# STM32F103Core.net
KiCad netlist of a schematic drawn in Altium Designer
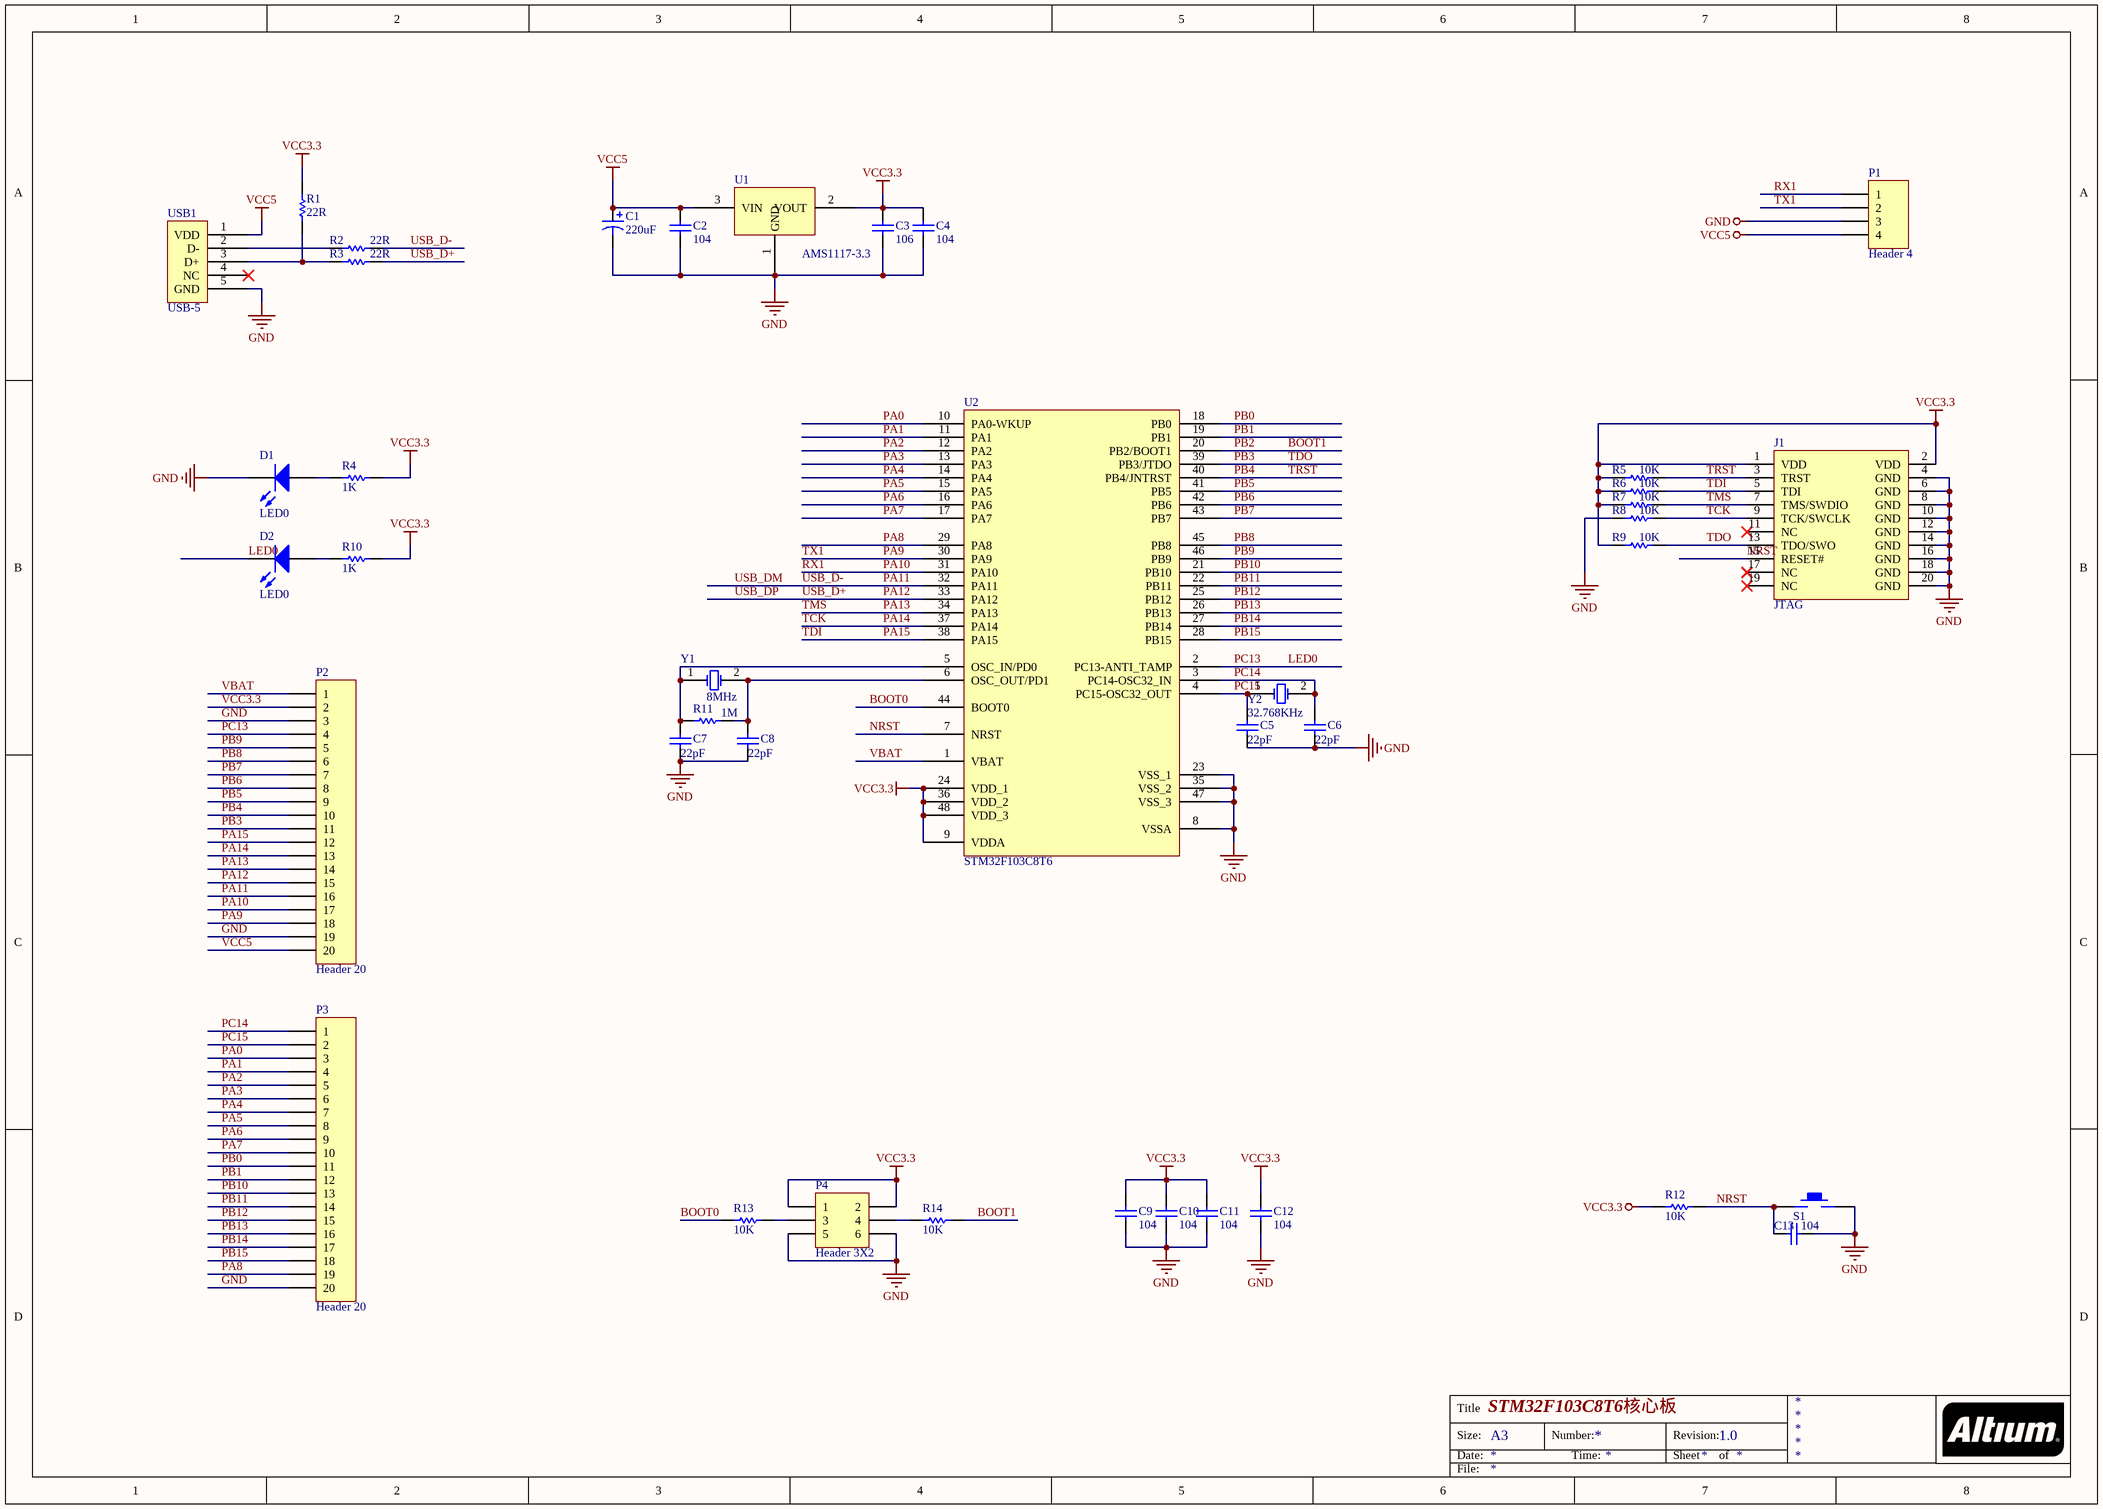
[diagram p0: STM32F103Core.SchDoc]

(export (version "E")
  (design (tool "Eeschema 10.0.6"))
  (components
    (comp (ref "C1")
      (value "220uF")
      (footprint "TAJ-B")
      (description "Cap Pol2")
      (fields (field (name "PUBLISHER") "Altium Limited"))
      (libsource (lib "STM32F103Core") (part "Cap Pol2"))
    )
    (comp (ref "C2")
      (value "104")
      (footprint "C0805")
      (description "Capacitor")
      (fields (field (name "PUBLISHER") "Altium Limited"))
      (libsource (lib "STM32F103Core") (part "C"))
    )
    (comp (ref "C3")
      (value "106")
      (footprint "C0805")
      (description "Capacitor")
      (fields (field (name "PUBLISHER") "Altium Limited"))
      (libsource (lib "STM32F103Core") (part "C"))
    )
    (comp (ref "C4")
      (value "104")
      (footprint "C0805")
      (description "Capacitor")
      (fields (field (name "PUBLISHER") "Altium Limited"))
      (libsource (lib "STM32F103Core") (part "C"))
    )
    (comp (ref "C5")
      (value "22pF")
      (footprint "C0805")
      (description "Capacitor")
      (fields (field (name "PUBLISHER") "Altium Limited"))
      (libsource (lib "STM32F103Core") (part "C"))
    )
    (comp (ref "C6")
      (value "22pF")
      (footprint "C0805")
      (description "Capacitor")
      (fields (field (name "PUBLISHER") "Altium Limited"))
      (libsource (lib "STM32F103Core") (part "C"))
    )
    (comp (ref "C7")
      (value "22pF")
      (footprint "C0805")
      (description "Capacitor")
      (fields (field (name "PUBLISHER") "Altium Limited"))
      (libsource (lib "STM32F103Core") (part "C"))
    )
    (comp (ref "C8")
      (value "22pF")
      (footprint "C0805")
      (description "Capacitor")
      (fields (field (name "PUBLISHER") "Altium Limited"))
      (libsource (lib "STM32F103Core") (part "C"))
    )
    (comp (ref "C9")
      (value "104")
      (footprint "C0805")
      (description "Capacitor")
      (fields (field (name "PUBLISHER") "Altium Limited"))
      (libsource (lib "STM32F103Core") (part "C"))
    )
    (comp (ref "C10")
      (value "104")
      (footprint "C0805")
      (description "Capacitor")
      (fields (field (name "PUBLISHER") "Altium Limited"))
      (libsource (lib "STM32F103Core") (part "C"))
    )
    (comp (ref "C11")
      (value "104")
      (footprint "C0805")
      (description "Capacitor")
      (fields (field (name "PUBLISHER") "Altium Limited"))
      (libsource (lib "STM32F103Core") (part "C"))
    )
    (comp (ref "C12")
      (value "104")
      (footprint "C0805")
      (description "Capacitor")
      (fields (field (name "PUBLISHER") "Altium Limited"))
      (libsource (lib "STM32F103Core") (part "C"))
    )
    (comp (ref "C13")
      (value "104")
      (footprint "C0805")
      (description "Capacitor")
      (fields (field (name "PUBLISHER") "Altium Limited"))
      (libsource (lib "STM32F103Core") (part "C"))
    )
    (comp (ref "D1")
      (value "LED0")
      (footprint "LED0805")
      (description "Typical INFRARED GaAs LED")
      (fields (field (name "PUBLISHER") "Altium Limited"))
      (libsource (lib "STM32F103Core") (part "LED0"))
    )
    (comp (ref "D2")
      (value "LED0")
      (footprint "LED0805")
      (description "Typical INFRARED GaAs LED")
      (fields (field (name "PUBLISHER") "Altium Limited"))
      (libsource (lib "STM32F103Core") (part "LED0"))
    )
    (comp (ref "J1") (value "JTAG") (footprint "DC3-20P-W") (libsource (lib "STM32F103Core") (part "JTAG")))
    (comp (ref "P1")
      (value "Header 4")
      (footprint "HDR1X4")
      (description "Header, 4-Pin")
      (fields (field (name "PUBLISHER") "Altium Limited"))
      (libsource (lib "STM32F103Core") (part "Header 4"))
    )
    (comp (ref "P2")
      (value "Header 20")
      (footprint "HDR1X20")
      (description "Header, 20-Pin")
      (fields (field (name "PUBLISHER") "Altium Limited"))
      (libsource (lib "STM32F103Core") (part "Header 20"))
    )
    (comp (ref "P3")
      (value "Header 20")
      (footprint "HDR1X20")
      (description "Header, 20-Pin")
      (fields (field (name "PUBLISHER") "Altium Limited"))
      (libsource (lib "STM32F103Core") (part "Header 20"))
    )
    (comp (ref "P4")
      (value "Header 3X2")
      (footprint "HDR2X3")
      (description "Header, 3-Pin, Dual row")
      (fields (field (name "PUBLISHER") "Altium Limited"))
      (libsource (lib "STM32F103Core") (part "Header 3X2"))
    )
    (comp (ref "R1")
      (value "22R")
      (footprint "R0805")
      (description "Resistor")
      (fields (field (name "PUBLISHER") "Altium Limited"))
      (libsource (lib "STM32F103Core") (part "R"))
    )
    (comp (ref "R2")
      (value "22R")
      (footprint "R0805")
      (description "Resistor")
      (fields (field (name "PUBLISHER") "Altium Limited"))
      (libsource (lib "STM32F103Core") (part "R"))
    )
    (comp (ref "R3")
      (value "22R")
      (footprint "R0805")
      (description "Resistor")
      (fields (field (name "PUBLISHER") "Altium Limited"))
      (libsource (lib "STM32F103Core") (part "R"))
    )
    (comp (ref "R4")
      (value "1K")
      (footprint "R0805")
      (description "Resistor")
      (fields (field (name "PUBLISHER") "Altium Limited"))
      (libsource (lib "STM32F103Core") (part "R"))
    )
    (comp (ref "R5")
      (value "10K")
      (footprint "R0805")
      (description "Resistor")
      (fields (field (name "PUBLISHER") "Altium Limited"))
      (libsource (lib "STM32F103Core") (part "R"))
    )
    (comp (ref "R6")
      (value "10K")
      (footprint "R0805")
      (description "Resistor")
      (fields (field (name "PUBLISHER") "Altium Limited"))
      (libsource (lib "STM32F103Core") (part "R"))
    )
    (comp (ref "R7")
      (value "10K")
      (footprint "R0805")
      (description "Resistor")
      (fields (field (name "PUBLISHER") "Altium Limited"))
      (libsource (lib "STM32F103Core") (part "R"))
    )
    (comp (ref "R8")
      (value "10K")
      (footprint "R0805")
      (description "Resistor")
      (fields (field (name "PUBLISHER") "Altium Limited"))
      (libsource (lib "STM32F103Core") (part "R"))
    )
    (comp (ref "R9")
      (value "10K")
      (footprint "R0805")
      (description "Resistor")
      (fields (field (name "PUBLISHER") "Altium Limited"))
      (libsource (lib "STM32F103Core") (part "R"))
    )
    (comp (ref "R10")
      (value "1K")
      (footprint "R0805")
      (description "Resistor")
      (fields (field (name "PUBLISHER") "Altium Limited"))
      (libsource (lib "STM32F103Core") (part "R"))
    )
    (comp (ref "R11")
      (value "1M")
      (footprint "R0805")
      (description "Resistor")
      (fields (field (name "PUBLISHER") "Altium Limited"))
      (libsource (lib "STM32F103Core") (part "R"))
    )
    (comp (ref "R12")
      (value "10K")
      (footprint "R0805")
      (description "Resistor")
      (fields (field (name "PUBLISHER") "Altium Limited"))
      (libsource (lib "STM32F103Core") (part "R"))
    )
    (comp (ref "R13")
      (value "10K")
      (footprint "R0805")
      (description "Resistor")
      (fields (field (name "PUBLISHER") "Altium Limited"))
      (libsource (lib "STM32F103Core") (part "R"))
    )
    (comp (ref "R14")
      (value "10K")
      (footprint "R0805")
      (description "Resistor")
      (fields (field (name "PUBLISHER") "Altium Limited"))
      (libsource (lib "STM32F103Core") (part "R"))
    )
    (comp (ref "S1")
      (value "KEY")
      (footprint "DSW-KFC-022S-H2.5")
      (description "普通轻触按钮")
      (libsource (lib "STM32F103Core") (part "KEY"))
    )
    (comp (ref "U1")
      (value "AMS1117-3.3")
      (footprint "SOT-223")
      (libsource (lib "STM32F103Core") (part "AMS1117"))
    )
    (comp (ref "U2")
      (value "STM32F103C8T6")
      (footprint "LQFP48_L")
      (libsource (lib "STM32F103Core") (part "STM32F103C8T6"))
    )
    (comp (ref "USB1")
      (value "USB-5")
      (footprint "USB-MicroUSB")
      (libsource (lib "STM32F103Core") (part "USB-5"))
    )
    (comp (ref "Y1")
      (value "8MHz")
      (footprint "49SMD")
      (description "Crystal Oscillator")
      (fields (field (name "PUBLISHER") "Altium Limited"))
      (libsource (lib "STM32F103Core") (part "XTAL"))
    )
    (comp (ref "Y2")
      (value "32.768KHz")
      (footprint "MC146")
      (description "Crystal Oscillator")
      (fields (field (name "PUBLISHER") "Altium Limited"))
      (libsource (lib "STM32F103Core") (part "XTAL"))
    )
  )
  (nets
    (net (code "1") (name "/BOOT0") (class "Default")
      (node (ref "R13") (pin "1") (pinfunction "1_1") (pintype "passive"))
      (node (ref "U2") (pin "44") (pinfunction "BOOT0_44") (pintype "passive"))
    )
    (net (code "2") (name "/BOOT1") (class "Default")
      (node (ref "R14") (pin "2") (pinfunction "2_2") (pintype "passive"))
      (node (ref "U2") (pin "20") (pinfunction "PB2/BOOT1_20") (pintype "passive"))
    )
    (net (code "3") (name "/LED0") (class "Default")
      (node (ref "D2") (pin "2") (pinfunction "K_2") (pintype "passive"))
      (node (ref "P2") (pin "4") (pinfunction "4_4") (pintype "passive"))
      (node (ref "U2") (pin "2") (pinfunction "PC13-ANTI_TAMP_2") (pintype "passive"))
    )
    (net (code "4") (name "/NRST") (class "Default")
      (node (ref "C13") (pin "1") (pinfunction "1_1") (pintype "passive"))
      (node (ref "J1") (pin "15") (pinfunction "RESET#_15") (pintype "passive"))
      (node (ref "R12") (pin "1") (pinfunction "1_1") (pintype "passive"))
      (node (ref "S1") (pin "1") (pinfunction "1_1") (pintype "passive"))
      (node (ref "U2") (pin "7") (pinfunction "NRST_7") (pintype "passive"))
    )
    (net (code "5") (name "/PA0") (class "Default")
      (node (ref "P3") (pin "3") (pinfunction "3_3") (pintype "passive"))
      (node (ref "U2") (pin "10") (pinfunction "PA0-WKUP_10") (pintype "passive"))
    )
    (net (code "6") (name "/PA1") (class "Default")
      (node (ref "P3") (pin "4") (pinfunction "4_4") (pintype "passive"))
      (node (ref "U2") (pin "11") (pinfunction "PA1_11") (pintype "passive"))
    )
    (net (code "7") (name "/PA2") (class "Default")
      (node (ref "P3") (pin "5") (pinfunction "5_5") (pintype "passive"))
      (node (ref "U2") (pin "12") (pinfunction "PA2_12") (pintype "passive"))
    )
    (net (code "8") (name "/PA3") (class "Default")
      (node (ref "P3") (pin "6") (pinfunction "6_6") (pintype "passive"))
      (node (ref "U2") (pin "13") (pinfunction "PA3_13") (pintype "passive"))
    )
    (net (code "9") (name "/PA4") (class "Default")
      (node (ref "P3") (pin "7") (pinfunction "7_7") (pintype "passive"))
      (node (ref "U2") (pin "14") (pinfunction "PA4_14") (pintype "passive"))
    )
    (net (code "10") (name "/PA5") (class "Default")
      (node (ref "P3") (pin "8") (pinfunction "8_8") (pintype "passive"))
      (node (ref "U2") (pin "15") (pinfunction "PA5_15") (pintype "passive"))
    )
    (net (code "11") (name "/PA6") (class "Default")
      (node (ref "P3") (pin "9") (pinfunction "9_9") (pintype "passive"))
      (node (ref "U2") (pin "16") (pinfunction "PA6_16") (pintype "passive"))
    )
    (net (code "12") (name "/PA7") (class "Default")
      (node (ref "P3") (pin "10") (pinfunction "10_10") (pintype "passive"))
      (node (ref "U2") (pin "17") (pinfunction "PA7_17") (pintype "passive"))
    )
    (net (code "13") (name "/PA8") (class "Default")
      (node (ref "P3") (pin "19") (pinfunction "19_19") (pintype "passive"))
      (node (ref "U2") (pin "29") (pinfunction "PA8_29") (pintype "passive"))
    )
    (net (code "14") (name "/PA9") (class "Default")
      (node (ref "P1") (pin "2") (pinfunction "2_2") (pintype "passive"))
      (node (ref "P2") (pin "18") (pinfunction "18_18") (pintype "passive"))
      (node (ref "U2") (pin "30") (pinfunction "PA9_30") (pintype "passive"))
    )
    (net (code "15") (name "/PA10") (class "Default")
      (node (ref "P1") (pin "1") (pinfunction "1_1") (pintype "passive"))
      (node (ref "P2") (pin "17") (pinfunction "17_17") (pintype "passive"))
      (node (ref "U2") (pin "31") (pinfunction "PA10_31") (pintype "passive"))
    )
    (net (code "16") (name "/PA11") (class "Default")
      (node (ref "P2") (pin "16") (pinfunction "16_16") (pintype "passive"))
      (node (ref "R2") (pin "2") (pinfunction "2_2") (pintype "passive"))
      (node (ref "U2") (pin "32") (pinfunction "PA11_32") (pintype "passive"))
    )
    (net (code "17") (name "/PA12") (class "Default")
      (node (ref "P2") (pin "15") (pinfunction "15_15") (pintype "passive"))
      (node (ref "R3") (pin "2") (pinfunction "2_2") (pintype "passive"))
      (node (ref "U2") (pin "33") (pinfunction "PA12_33") (pintype "passive"))
    )
    (net (code "18") (name "/PA13") (class "Default")
      (node (ref "J1") (pin "7") (pinfunction "TMS/SWDIO_7") (pintype "passive"))
      (node (ref "P2") (pin "14") (pinfunction "14_14") (pintype "passive"))
      (node (ref "R7") (pin "2") (pinfunction "2_2") (pintype "passive"))
      (node (ref "U2") (pin "34") (pinfunction "PA13_34") (pintype "passive"))
    )
    (net (code "19") (name "/PA14") (class "Default")
      (node (ref "J1") (pin "9") (pinfunction "TCK/SWCLK_9") (pintype "passive"))
      (node (ref "P2") (pin "13") (pinfunction "13_13") (pintype "passive"))
      (node (ref "R8") (pin "2") (pinfunction "2_2") (pintype "passive"))
      (node (ref "U2") (pin "37") (pinfunction "PA14_37") (pintype "passive"))
    )
    (net (code "20") (name "/PA15") (class "Default")
      (node (ref "J1") (pin "5") (pinfunction "TDI_5") (pintype "passive"))
      (node (ref "P2") (pin "12") (pinfunction "12_12") (pintype "passive"))
      (node (ref "R6") (pin "2") (pinfunction "2_2") (pintype "passive"))
      (node (ref "U2") (pin "38") (pinfunction "PA15_38") (pintype "passive"))
    )
    (net (code "21") (name "/PB0") (class "Default")
      (node (ref "P3") (pin "11") (pinfunction "11_11") (pintype "passive"))
      (node (ref "U2") (pin "18") (pinfunction "PB0_18") (pintype "passive"))
    )
    (net (code "22") (name "/PB1") (class "Default")
      (node (ref "P3") (pin "12") (pinfunction "12_12") (pintype "passive"))
      (node (ref "U2") (pin "19") (pinfunction "PB1_19") (pintype "passive"))
    )
    (net (code "23") (name "/PB3") (class "Default")
      (node (ref "J1") (pin "13") (pinfunction "TDO/SWO_13") (pintype "passive"))
      (node (ref "P2") (pin "11") (pinfunction "11_11") (pintype "passive"))
      (node (ref "R9") (pin "2") (pinfunction "2_2") (pintype "passive"))
      (node (ref "U2") (pin "39") (pinfunction "PB3/JTDO_39") (pintype "passive"))
    )
    (net (code "24") (name "/PB4") (class "Default")
      (node (ref "J1") (pin "3") (pinfunction "TRST_3") (pintype "passive"))
      (node (ref "P2") (pin "10") (pinfunction "10_10") (pintype "passive"))
      (node (ref "R5") (pin "2") (pinfunction "2_2") (pintype "passive"))
      (node (ref "U2") (pin "40") (pinfunction "PB4/JNTRST_40") (pintype "passive"))
    )
    (net (code "25") (name "/PB5") (class "Default")
      (node (ref "P2") (pin "9") (pinfunction "9_9") (pintype "passive"))
      (node (ref "U2") (pin "41") (pinfunction "PB5_41") (pintype "passive"))
    )
    (net (code "26") (name "/PB6") (class "Default")
      (node (ref "P2") (pin "8") (pinfunction "8_8") (pintype "passive"))
      (node (ref "U2") (pin "42") (pinfunction "PB6_42") (pintype "passive"))
    )
    (net (code "27") (name "/PB7") (class "Default")
      (node (ref "P2") (pin "7") (pinfunction "7_7") (pintype "passive"))
      (node (ref "U2") (pin "43") (pinfunction "PB7_43") (pintype "passive"))
    )
    (net (code "28") (name "/PB8") (class "Default")
      (node (ref "P2") (pin "6") (pinfunction "6_6") (pintype "passive"))
      (node (ref "U2") (pin "45") (pinfunction "PB8_45") (pintype "passive"))
    )
    (net (code "29") (name "/PB9") (class "Default")
      (node (ref "P2") (pin "5") (pinfunction "5_5") (pintype "passive"))
      (node (ref "U2") (pin "46") (pinfunction "PB9_46") (pintype "passive"))
    )
    (net (code "30") (name "/PB10") (class "Default")
      (node (ref "P3") (pin "13") (pinfunction "13_13") (pintype "passive"))
      (node (ref "U2") (pin "21") (pinfunction "PB10_21") (pintype "passive"))
    )
    (net (code "31") (name "/PB11") (class "Default")
      (node (ref "P3") (pin "14") (pinfunction "14_14") (pintype "passive"))
      (node (ref "U2") (pin "22") (pinfunction "PB11_22") (pintype "passive"))
    )
    (net (code "32") (name "/PB12") (class "Default")
      (node (ref "P3") (pin "15") (pinfunction "15_15") (pintype "passive"))
      (node (ref "U2") (pin "25") (pinfunction "PB12_25") (pintype "passive"))
    )
    (net (code "33") (name "/PB13") (class "Default")
      (node (ref "P3") (pin "16") (pinfunction "16_16") (pintype "passive"))
      (node (ref "U2") (pin "26") (pinfunction "PB13_26") (pintype "passive"))
    )
    (net (code "34") (name "/PB14") (class "Default")
      (node (ref "P3") (pin "17") (pinfunction "17_17") (pintype "passive"))
      (node (ref "U2") (pin "27") (pinfunction "PB14_27") (pintype "passive"))
    )
    (net (code "35") (name "/PB15") (class "Default")
      (node (ref "P3") (pin "18") (pinfunction "18_18") (pintype "passive"))
      (node (ref "U2") (pin "28") (pinfunction "PB15_28") (pintype "passive"))
    )
    (net (code "36") (name "/PC14") (class "Default")
      (node (ref "C6") (pin "2") (pinfunction "2_2") (pintype "passive"))
      (node (ref "P3") (pin "1") (pinfunction "1_1") (pintype "passive"))
      (node (ref "U2") (pin "3") (pinfunction "PC14-OSC32_IN_3") (pintype "passive"))
      (node (ref "Y2") (pin "2") (pinfunction "OSC2_2") (pintype "passive"))
    )
    (net (code "37") (name "/PC15") (class "Default")
      (node (ref "C5") (pin "2") (pinfunction "2_2") (pintype "passive"))
      (node (ref "P3") (pin "2") (pinfunction "2_2") (pintype "passive"))
      (node (ref "U2") (pin "4") (pinfunction "PC15-OSC32_OUT_4") (pintype "passive"))
      (node (ref "Y2") (pin "1") (pinfunction "OSC1_1") (pintype "passive"))
    )
    (net (code "38") (name "/VBAT") (class "Default")
      (node (ref "P2") (pin "1") (pinfunction "1_1") (pintype "passive"))
      (node (ref "U2") (pin "1") (pinfunction "VBAT_1") (pintype "passive"))
    )
    (net (code "39") (name "GND") (class "Default")
      (node (ref "C1") (pin "2") (pinfunction "2_2") (pintype "passive"))
      (node (ref "C10") (pin "1") (pinfunction "1_1") (pintype "passive"))
      (node (ref "C11") (pin "1") (pinfunction "1_1") (pintype "passive"))
      (node (ref "C12") (pin "1") (pinfunction "1_1") (pintype "passive"))
      (node (ref "C13") (pin "2") (pinfunction "2_2") (pintype "passive"))
      (node (ref "C2") (pin "1") (pinfunction "1_1") (pintype "passive"))
      (node (ref "C3") (pin "1") (pinfunction "1_1") (pintype "passive"))
      (node (ref "C4") (pin "1") (pinfunction "1_1") (pintype "passive"))
      (node (ref "C5") (pin "1") (pinfunction "1_1") (pintype "passive"))
      (node (ref "C6") (pin "1") (pinfunction "1_1") (pintype "passive"))
      (node (ref "C7") (pin "1") (pinfunction "1_1") (pintype "passive"))
      (node (ref "C8") (pin "1") (pinfunction "1_1") (pintype "passive"))
      (node (ref "C9") (pin "1") (pinfunction "1_1") (pintype "passive"))
      (node (ref "D1") (pin "2") (pinfunction "K_2") (pintype "passive"))
      (node (ref "J1") (pin "10") (pinfunction "GND_10") (pintype "passive"))
      (node (ref "J1") (pin "12") (pinfunction "GND_12") (pintype "passive"))
      (node (ref "J1") (pin "14") (pinfunction "GND_14") (pintype "passive"))
      (node (ref "J1") (pin "16") (pinfunction "GND_16") (pintype "passive"))
      (node (ref "J1") (pin "18") (pinfunction "GND_18") (pintype "passive"))
      (node (ref "J1") (pin "20") (pinfunction "GND_20") (pintype "passive"))
      (node (ref "J1") (pin "4") (pinfunction "GND_4") (pintype "passive"))
      (node (ref "J1") (pin "6") (pinfunction "GND_6") (pintype "passive"))
      (node (ref "J1") (pin "8") (pinfunction "GND_8") (pintype "passive"))
      (node (ref "P1") (pin "3") (pinfunction "3_3") (pintype "passive"))
      (node (ref "P2") (pin "19") (pinfunction "19_19") (pintype "passive"))
      (node (ref "P2") (pin "3") (pinfunction "3_3") (pintype "passive"))
      (node (ref "P3") (pin "20") (pinfunction "20_20") (pintype "passive"))
      (node (ref "P4") (pin "5") (pinfunction "5_5") (pintype "passive"))
      (node (ref "P4") (pin "6") (pinfunction "6_6") (pintype "passive"))
      (node (ref "R8") (pin "1") (pinfunction "1_1") (pintype "passive"))
      (node (ref "S1") (pin "2") (pinfunction "2_2") (pintype "passive"))
      (node (ref "U1") (pin "1") (pinfunction "GND_1") (pintype "passive"))
      (node (ref "U2") (pin "23") (pinfunction "VSS_1_23") (pintype "passive"))
      (node (ref "U2") (pin "35") (pinfunction "VSS_2_35") (pintype "passive"))
      (node (ref "U2") (pin "47") (pinfunction "VSS_3_47") (pintype "passive"))
      (node (ref "U2") (pin "8") (pinfunction "VSSA_8") (pintype "passive"))
      (node (ref "USB1") (pin "5") (pinfunction "GND_5") (pintype "passive"))
    )
    (net (code "40") (name "Net-(D1-A)") (class "Default")
      (node (ref "D1") (pin "1") (pinfunction "A_1") (pintype "passive"))
      (node (ref "R4") (pin "1") (pinfunction "1_1") (pintype "passive"))
    )
    (net (code "41") (name "Net-(D2-A)") (class "Default")
      (node (ref "D2") (pin "1") (pinfunction "A_1") (pintype "passive"))
      (node (ref "R10") (pin "1") (pinfunction "1_1") (pintype "passive"))
    )
    (net (code "42") (name "Net-(P4-Pad3)") (class "Default")
      (node (ref "P4") (pin "3") (pinfunction "3_3") (pintype "passive"))
      (node (ref "R13") (pin "2") (pinfunction "2_2") (pintype "passive"))
    )
    (net (code "43") (name "Net-(P4-Pad4)") (class "Default")
      (node (ref "P4") (pin "4") (pinfunction "4_4") (pintype "passive"))
      (node (ref "R14") (pin "1") (pinfunction "1_1") (pintype "passive"))
    )
    (net (code "44") (name "Net-(U2-OSC_IN{slash}PD0)") (class "Default")
      (node (ref "C7") (pin "2") (pinfunction "2_2") (pintype "passive"))
      (node (ref "R11") (pin "1") (pinfunction "1_1") (pintype "passive"))
      (node (ref "U2") (pin "5") (pinfunction "OSC_IN/PD0_5") (pintype "passive"))
      (node (ref "Y1") (pin "1") (pinfunction "OSC1_1") (pintype "passive"))
    )
    (net (code "45") (name "Net-(U2-OSC_OUT{slash}PD1)") (class "Default")
      (node (ref "C8") (pin "2") (pinfunction "2_2") (pintype "passive"))
      (node (ref "R11") (pin "2") (pinfunction "2_2") (pintype "passive"))
      (node (ref "U2") (pin "6") (pinfunction "OSC_OUT/PD1_6") (pintype "passive"))
      (node (ref "Y1") (pin "2") (pinfunction "OSC2_2") (pintype "passive"))
    )
    (net (code "46") (name "Net-(USB1-D+)") (class "Default")
      (node (ref "R1") (pin "1") (pinfunction "1_1") (pintype "passive"))
      (node (ref "R3") (pin "1") (pinfunction "1_1") (pintype "passive"))
      (node (ref "USB1") (pin "3") (pinfunction "D+_3") (pintype "passive"))
    )
    (net (code "47") (name "Net-(USB1-D-)") (class "Default")
      (node (ref "R2") (pin "1") (pinfunction "1_1") (pintype "passive"))
      (node (ref "USB1") (pin "2") (pinfunction "D-_2") (pintype "passive"))
    )
    (net (code "48") (name "VCC3.3") (class "Default")
      (node (ref "C10") (pin "2") (pinfunction "2_2") (pintype "passive"))
      (node (ref "C11") (pin "2") (pinfunction "2_2") (pintype "passive"))
      (node (ref "C12") (pin "2") (pinfunction "2_2") (pintype "passive"))
      (node (ref "C3") (pin "2") (pinfunction "2_2") (pintype "passive"))
      (node (ref "C4") (pin "2") (pinfunction "2_2") (pintype "passive"))
      (node (ref "C9") (pin "2") (pinfunction "2_2") (pintype "passive"))
      (node (ref "J1") (pin "1") (pinfunction "VDD_1") (pintype "passive"))
      (node (ref "J1") (pin "2") (pinfunction "VDD_2") (pintype "passive"))
      (node (ref "P2") (pin "2") (pinfunction "2_2") (pintype "passive"))
      (node (ref "P4") (pin "1") (pinfunction "1_1") (pintype "passive"))
      (node (ref "P4") (pin "2") (pinfunction "2_2") (pintype "passive"))
      (node (ref "R1") (pin "2") (pinfunction "2_2") (pintype "passive"))
      (node (ref "R10") (pin "2") (pinfunction "2_2") (pintype "passive"))
      (node (ref "R12") (pin "2") (pinfunction "2_2") (pintype "passive"))
      (node (ref "R4") (pin "2") (pinfunction "2_2") (pintype "passive"))
      (node (ref "R5") (pin "1") (pinfunction "1_1") (pintype "passive"))
      (node (ref "R6") (pin "1") (pinfunction "1_1") (pintype "passive"))
      (node (ref "R7") (pin "1") (pinfunction "1_1") (pintype "passive"))
      (node (ref "R9") (pin "1") (pinfunction "1_1") (pintype "passive"))
      (node (ref "U1") (pin "2") (pinfunction "VOUT_2") (pintype "passive"))
      (node (ref "U2") (pin "24") (pinfunction "VDD_1_24") (pintype "passive"))
      (node (ref "U2") (pin "36") (pinfunction "VDD_2_36") (pintype "passive"))
      (node (ref "U2") (pin "48") (pinfunction "VDD_3_48") (pintype "passive"))
      (node (ref "U2") (pin "9") (pinfunction "VDDA_9") (pintype "passive"))
    )
    (net (code "49") (name "VCC5") (class "Default")
      (node (ref "C1") (pin "1") (pinfunction "1_1") (pintype "passive"))
      (node (ref "C2") (pin "2") (pinfunction "2_2") (pintype "passive"))
      (node (ref "P1") (pin "4") (pinfunction "4_4") (pintype "passive"))
      (node (ref "P2") (pin "20") (pinfunction "20_20") (pintype "passive"))
      (node (ref "U1") (pin "3") (pinfunction "VIN_3") (pintype "passive"))
      (node (ref "USB1") (pin "1") (pinfunction "VDD_1") (pintype "passive"))
    )
    (net (code "50") (name "unconnected-(J1-NC-Pad11)") (class "Default")
      (node (ref "J1") (pin "11") (pinfunction "NC_11") (pintype "passive+no_connect"))
    )
    (net (code "51") (name "unconnected-(J1-NC-Pad17)") (class "Default")
      (node (ref "J1") (pin "17") (pinfunction "NC_17") (pintype "passive+no_connect"))
    )
    (net (code "52") (name "unconnected-(J1-NC-Pad19)") (class "Default")
      (node (ref "J1") (pin "19") (pinfunction "NC_19") (pintype "passive+no_connect"))
    )
    (net (code "53") (name "unconnected-(USB1-NC-Pad4)") (class "Default")
      (node (ref "USB1") (pin "4") (pinfunction "NC_4") (pintype "passive+no_connect"))
    )
  )
)
